# 07_-_USB-C_Connector.net
KiCad netlist of a schematic drawn in Altium Designer
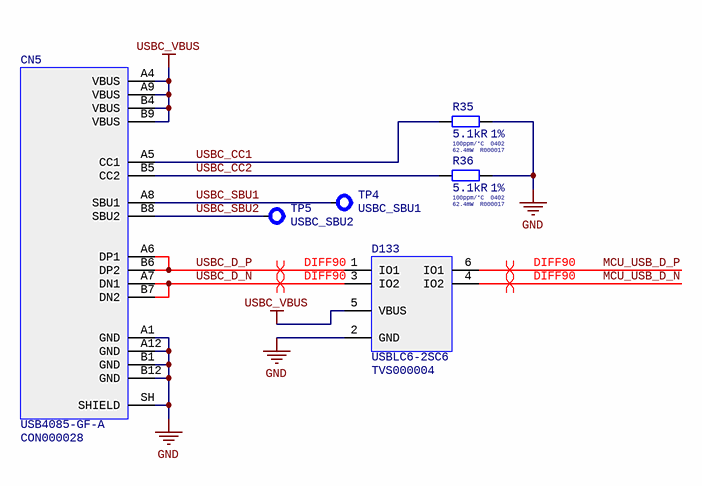
[diagram p0: [07] - USB-C Connector.SchDoc]

(export (version "E")
  (design (tool "Eeschema 10.0.6"))
  (components
    (comp (ref "CN5")
      (value "USB4085-GF-A")
      (footprint "CON-THT-USB-C-16POS-USB4085-GCT")
      (description "CON USB TYPE C THROUGH HOLE 16POS")
      (fields
        (field (name "MANUFACTURER") "Global Connector Technology")
        (field (name "INTERNAL PART NUMBER") "CON000028")
      )
      (libsource (lib "Altium_Lib_Standard") (part "USB4085-GF-A"))
    )
    (comp (ref "D133")
      (value "USBLC6-2SC6")
      (footprint "SOT-23-6L-H1.45MM-ST")
      (description "TVS DIODE 2CH 5.25V 17V USB2.0 SOT23-6L")
      (fields
        (field (name "MANUFACTURER") "STMicroelectronics")
        (field (name "INTERNAL PART NUMBER") "TVS000004")
      )
      (libsource (lib "Altium_Lib_Standard") (part "USBLC6-2SC6"))
    )
    (comp (ref "R35")
      (value "RC0402FR-075K1L")
      (footprint "RES-SMD-0402-0.4MM-IPC-MED")
      (description "RES 5K1 1% 1/16W SMD 0402 YAEGO")
      (fields
        (field (name "MANUFACTURER") "Yageo")
        (field (name "CASE/PACKAGE") "0402")
        (field (name "RESISTANCE") "5.1kR")
        (field (name "TEMPERATURE COEFFICIENT") "100ppm/°C")
        (field (name "TOLERANCE") "1%")
        (field (name "MAX POWER DISSIPATION") "62.4mW")
        (field (name "INTERNAL PART NUMBER") "R000017")
      )
      (libsource (lib "Altium_Lib_Standard") (part "RC0402FR-075K1L"))
    )
    (comp (ref "R36")
      (value "RC0402FR-075K1L")
      (footprint "RES-SMD-0402-0.4MM-IPC-MED")
      (description "RES 5K1 1% 1/16W SMD 0402 YAEGO")
      (fields
        (field (name "MANUFACTURER") "Yageo")
        (field (name "CASE/PACKAGE") "0402")
        (field (name "RESISTANCE") "5.1kR")
        (field (name "TEMPERATURE COEFFICIENT") "100ppm/°C")
        (field (name "TOLERANCE") "1%")
        (field (name "MAX POWER DISSIPATION") "62.4mW")
        (field (name "INTERNAL PART NUMBER") "R000017")
      )
      (libsource (lib "Altium_Lib_Standard") (part "RC0402FR-075K1L"))
    )
    (comp (ref "TP4")
      (value "USBC_SBU1")
      (footprint "TP-SMD-CIRCULAR-1MM")
      (libsource (lib "Altium_Lib_Standard") (part "TESTPOINT_CIRCULAR_1MM"))
    )
    (comp (ref "TP5")
      (value "USBC_SBU2")
      (footprint "TP-SMD-CIRCULAR-1MM")
      (libsource (lib "Altium_Lib_Standard") (part "TESTPOINT_CIRCULAR_1MM"))
    )
  )
  (nets
    (net (code "1") (name "/MCU_USB_D_N") (class "Default")
      (node (ref "D133") (pin "4") (pinfunction "IO2_4") (pintype "passive"))
    )
    (net (code "2") (name "/MCU_USB_D_P") (class "Default")
      (node (ref "D133") (pin "6") (pinfunction "IO1_6") (pintype "passive"))
    )
    (net (code "3") (name "/USBC_CC1") (class "Default")
      (node (ref "CN5") (pin "A5") (pinfunction "CC1_A5") (pintype "passive"))
      (node (ref "R35") (pin "1") (pinfunction "1_1") (pintype "passive"))
    )
    (net (code "4") (name "/USBC_CC2") (class "Default")
      (node (ref "CN5") (pin "B5") (pinfunction "CC2_B5") (pintype "passive"))
      (node (ref "R36") (pin "1") (pinfunction "1_1") (pintype "passive"))
    )
    (net (code "5") (name "/USBC_D_N") (class "Default")
      (node (ref "CN5") (pin "A7") (pinfunction "DN1_A7") (pintype "passive"))
      (node (ref "CN5") (pin "B7") (pinfunction "DN2_B7") (pintype "passive"))
      (node (ref "D133") (pin "3") (pinfunction "IO2_3") (pintype "passive"))
    )
    (net (code "6") (name "/USBC_D_P") (class "Default")
      (node (ref "CN5") (pin "A6") (pinfunction "DP1_A6") (pintype "passive"))
      (node (ref "CN5") (pin "B6") (pinfunction "DP2_B6") (pintype "passive"))
      (node (ref "D133") (pin "1") (pinfunction "IO1_1") (pintype "passive"))
    )
    (net (code "7") (name "/USBC_SBU1") (class "Default")
      (node (ref "CN5") (pin "A8") (pinfunction "SBU1_A8") (pintype "passive"))
      (node (ref "TP4") (pin "1") (pinfunction "1_1") (pintype "passive"))
    )
    (net (code "8") (name "/USBC_SBU2") (class "Default")
      (node (ref "CN5") (pin "B8") (pinfunction "SBU2_B8") (pintype "passive"))
      (node (ref "TP5") (pin "1") (pinfunction "1_1") (pintype "passive"))
    )
    (net (code "9") (name "GND") (class "Default")
      (node (ref "CN5") (pin "A1") (pinfunction "GND_A1") (pintype "passive"))
      (node (ref "CN5") (pin "A12") (pinfunction "GND_A12") (pintype "passive"))
      (node (ref "CN5") (pin "B1") (pinfunction "GND_B1") (pintype "passive"))
      (node (ref "CN5") (pin "B12") (pinfunction "GND_B12") (pintype "passive"))
      (node (ref "CN5") (pin "SH") (pinfunction "SHIELD_SH") (pintype "passive"))
      (node (ref "D133") (pin "2") (pinfunction "GND_2") (pintype "power_in"))
      (node (ref "R35") (pin "2") (pinfunction "2_2") (pintype "passive"))
      (node (ref "R36") (pin "2") (pinfunction "2_2") (pintype "passive"))
    )
    (net (code "10") (name "USBC_VBUS") (class "Default")
      (node (ref "CN5") (pin "A4") (pinfunction "VBUS_A4") (pintype "passive"))
      (node (ref "CN5") (pin "A9") (pinfunction "VBUS_A9") (pintype "passive"))
      (node (ref "CN5") (pin "B4") (pinfunction "VBUS_B4") (pintype "passive"))
      (node (ref "CN5") (pin "B9") (pinfunction "VBUS_B9") (pintype "passive"))
      (node (ref "D133") (pin "5") (pinfunction "VBUS_5") (pintype "power_in"))
    )
  )
)
